# Remote.net
KiCad netlist of a schematic drawn in Altium Designer
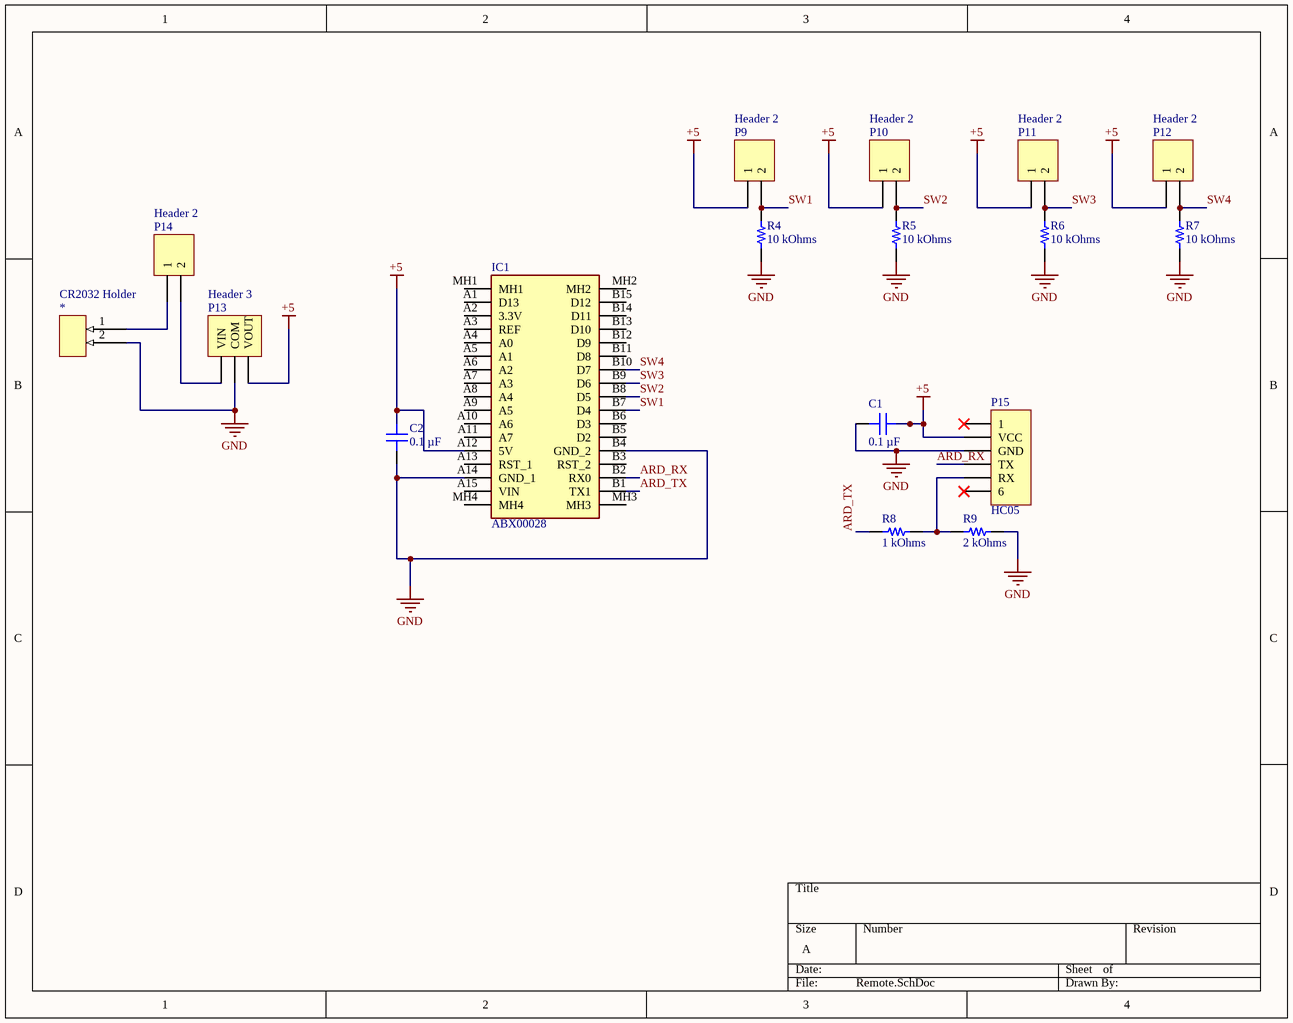
[diagram p0: Remote.SchDoc]

(export (version "E")
  (design (tool "Eeschema 10.0.6"))
  (components
    (comp (ref "*")
      (value "CR2032 Holder")
      (footprint "CR2032 Holder-Footprint-1")
      (description "Coin cell battery holder")
      (libsource (lib "Donados") (part "CR2032 Holder-Symbol-1"))
    )
    (comp (ref "C1")
      (value "0.1 µF")
      (footprint "CAP 1206_3216 - 0.8MM")
      (description "CAP CER 0.1UF 50V Y5V 1206")
      (fields (field (name "PART NUMBER") "CC1206MRY5V9BB104") (field (name "MANUFACTURER") "Yageo"))
      (libsource (lib "Celestial Altium Library - altium_library") (part "Capacitor"))
    )
    (comp (ref "C2")
      (value "0.1 µF")
      (footprint "CAP 1206_3216 - 0.8MM")
      (description "CAP CER 0.1UF 50V Y5V 1206")
      (fields (field (name "PART NUMBER") "CC1206MRY5V9BB104") (field (name "MANUFACTURER") "Yageo"))
      (libsource (lib "Celestial Altium Library - altium_library") (part "Capacitor"))
    )
    (comp (ref "IC1")
      (value "ABX00028")
      (footprint "SamacSys:ABX00028")
      (description "Integrated Circuit")
      (fields (field (name "MOUSER PART NUMBER") "782-ABX00028"))
      (libsource (lib "*") (part "ABX00028"))
    )
    (comp (ref "P9")
      (value "Header 2")
      (footprint "HDR1X2")
      (description "Header, 2-Pin")
      (fields (field (name "PUBLISHER") "Altium Limited"))
      (libsource (lib "Miscellaneous Connectors") (part "Header 2"))
    )
    (comp (ref "P10")
      (value "Header 2")
      (footprint "HDR1X2")
      (description "Header, 2-Pin")
      (fields (field (name "PUBLISHER") "Altium Limited"))
      (libsource (lib "Miscellaneous Connectors") (part "Header 2"))
    )
    (comp (ref "P11")
      (value "Header 2")
      (footprint "HDR1X2")
      (description "Header, 2-Pin")
      (fields (field (name "PUBLISHER") "Altium Limited"))
      (libsource (lib "Miscellaneous Connectors") (part "Header 2"))
    )
    (comp (ref "P12")
      (value "Header 2")
      (footprint "HDR1X2")
      (description "Header, 2-Pin")
      (fields (field (name "PUBLISHER") "Altium Limited"))
      (libsource (lib "Miscellaneous Connectors") (part "Header 2"))
    )
    (comp (ref "P13")
      (value "Header 3")
      (footprint "HDR1X3")
      (description "Header, 3-Pin")
      (fields (field (name "PUBLISHER") "Altium Limited"))
      (libsource (lib "Miscellaneous Connectors") (part "Header 3"))
    )
    (comp (ref "P14")
      (value "Header 2")
      (footprint "HDR1X2")
      (description "Header, 2-Pin")
      (fields (field (name "PUBLISHER") "Altium Limited"))
      (libsource (lib "Miscellaneous Connectors") (part "Header 2"))
    )
    (comp (ref "P15")
      (value "HC05")
      (footprint "HDR1X6")
      (description "Header, 6-Pin")
      (fields (field (name "PUBLISHER") "Altium Limited"))
      (libsource (lib "Miscellaneous Connectors") (part "Header 6"))
    )
    (comp (ref "R4")
      (value "10 kOhms")
      (footprint "RES 1206_3216")
      (description "RES SMD 10K OHM 1% 1/4W 1206")
      (fields
        (field (name "PART NUMBER") "CRG1206F10K")
        (field (name "MANUFACTURER") "TE Connectivity Passive Product")
      )
      (libsource (lib "Celestial Altium Library - altium_library") (part "Resistor"))
    )
    (comp (ref "R5")
      (value "10 kOhms")
      (footprint "RES 1206_3216")
      (description "RES SMD 10K OHM 1% 1/4W 1206")
      (fields
        (field (name "PART NUMBER") "CRG1206F10K")
        (field (name "MANUFACTURER") "TE Connectivity Passive Product")
      )
      (libsource (lib "Celestial Altium Library - altium_library") (part "Resistor"))
    )
    (comp (ref "R6")
      (value "10 kOhms")
      (footprint "RES 1206_3216")
      (description "RES SMD 10K OHM 1% 1/4W 1206")
      (fields
        (field (name "PART NUMBER") "CRG1206F10K")
        (field (name "MANUFACTURER") "TE Connectivity Passive Product")
      )
      (libsource (lib "Celestial Altium Library - altium_library") (part "Resistor"))
    )
    (comp (ref "R7")
      (value "10 kOhms")
      (footprint "RES 1206_3216")
      (description "RES SMD 10K OHM 1% 1/4W 1206")
      (fields
        (field (name "PART NUMBER") "CRG1206F10K")
        (field (name "MANUFACTURER") "TE Connectivity Passive Product")
      )
      (libsource (lib "Celestial Altium Library - altium_library") (part "Resistor"))
    )
    (comp (ref "R8")
      (value "1 kOhms")
      (footprint "RES 1206_3216")
      (description "RES 1K OHM 0.1% 1/8W 1206")
      (fields
        (field (name "PART NUMBER") "RNCS1206BKE1K00")
        (field (name "MANUFACTURER") "Stackpole Electronics Inc")
      )
      (libsource (lib "Celestial Altium Library - altium_library") (part "Resistor"))
    )
    (comp (ref "R9")
      (value "2 kOhms")
      (footprint "RES 1206_3216")
      (description "RES SMD 2K OHM 5% 1/4W 1206")
      (fields (field (name "PART NUMBER") "AC1206JR-072KL") (field (name "MANUFACTURER") "Yageo"))
      (libsource (lib "Celestial Altium Library - altium_library") (part "Resistor"))
    )
  )
  (nets
    (net (code "1") (name "+5") (class "Default")
      (node (ref "C1") (pin "2") (pinfunction "2_2") (pintype "passive"))
      (node (ref "C2") (pin "2") (pinfunction "2_2") (pintype "passive"))
      (node (ref "IC1") (pin "A12") (pinfunction "5V_A12") (pintype "passive"))
      (node (ref "P10") (pin "1") (pinfunction "1_1") (pintype "passive"))
      (node (ref "P11") (pin "1") (pinfunction "1_1") (pintype "passive"))
      (node (ref "P12") (pin "1") (pinfunction "1_1") (pintype "passive"))
      (node (ref "P13") (pin "3") (pinfunction "VOUT_3") (pintype "passive"))
      (node (ref "P15") (pin "2") (pinfunction "VCC_2") (pintype "passive"))
      (node (ref "P9") (pin "1") (pinfunction "1_1") (pintype "passive"))
    )
    (net (code "2") (name "/ARD_RX") (class "Default")
      (node (ref "IC1") (pin "B2") (pinfunction "RX0_B2") (pintype "passive"))
      (node (ref "P15") (pin "4") (pinfunction "TX_4") (pintype "passive"))
    )
    (net (code "3") (name "/ARD_TX") (class "Default")
      (node (ref "IC1") (pin "B1") (pinfunction "TX1_B1") (pintype "passive"))
      (node (ref "R8") (pin "1") (pinfunction "1_1") (pintype "passive"))
    )
    (net (code "4") (name "/SW1") (class "Default")
      (node (ref "IC1") (pin "B7") (pinfunction "D4_B7") (pintype "passive"))
      (node (ref "P9") (pin "2") (pinfunction "2_2") (pintype "passive"))
      (node (ref "R4") (pin "2") (pinfunction "2_2") (pintype "passive"))
    )
    (net (code "5") (name "/SW2") (class "Default")
      (node (ref "IC1") (pin "B8") (pinfunction "D5_B8") (pintype "passive"))
      (node (ref "P10") (pin "2") (pinfunction "2_2") (pintype "passive"))
      (node (ref "R5") (pin "2") (pinfunction "2_2") (pintype "passive"))
    )
    (net (code "6") (name "/SW3") (class "Default")
      (node (ref "IC1") (pin "B9") (pinfunction "D6_B9") (pintype "passive"))
      (node (ref "P11") (pin "2") (pinfunction "2_2") (pintype "passive"))
      (node (ref "R6") (pin "2") (pinfunction "2_2") (pintype "passive"))
    )
    (net (code "7") (name "/SW4") (class "Default")
      (node (ref "IC1") (pin "B10") (pinfunction "D7_B10") (pintype "passive"))
      (node (ref "P12") (pin "2") (pinfunction "2_2") (pintype "passive"))
      (node (ref "R7") (pin "2") (pinfunction "2_2") (pintype "passive"))
    )
    (net (code "8") (name "GND") (class "Default")
      (node (ref "*") (pin "2") (pintype "input"))
      (node (ref "C1") (pin "1") (pinfunction "1_1") (pintype "passive"))
      (node (ref "C2") (pin "1") (pinfunction "1_1") (pintype "passive"))
      (node (ref "IC1") (pin "A14") (pinfunction "GND_1_A14") (pintype "passive"))
      (node (ref "IC1") (pin "B4") (pinfunction "GND_2_B4") (pintype "passive"))
      (node (ref "P13") (pin "2") (pinfunction "COM_2") (pintype "passive"))
      (node (ref "P15") (pin "3") (pinfunction "GND_3") (pintype "passive"))
      (node (ref "R4") (pin "1") (pinfunction "1_1") (pintype "passive"))
      (node (ref "R5") (pin "1") (pinfunction "1_1") (pintype "passive"))
      (node (ref "R6") (pin "1") (pinfunction "1_1") (pintype "passive"))
      (node (ref "R7") (pin "1") (pinfunction "1_1") (pintype "passive"))
      (node (ref "R9") (pin "2") (pinfunction "2_2") (pintype "passive"))
    )
    (net (code "9") (name "Net-(*-Pad1)") (class "Default")
      (node (ref "*") (pin "1") (pintype "input"))
      (node (ref "P14") (pin "1") (pinfunction "1_1") (pintype "passive"))
    )
    (net (code "10") (name "Net-(P13-VIN)") (class "Default")
      (node (ref "P13") (pin "1") (pinfunction "VIN_1") (pintype "passive"))
      (node (ref "P14") (pin "2") (pinfunction "2_2") (pintype "passive"))
    )
    (net (code "11") (name "Net-(P15-RX)") (class "Default")
      (node (ref "P15") (pin "5") (pinfunction "RX_5") (pintype "passive"))
      (node (ref "R8") (pin "2") (pinfunction "2_2") (pintype "passive"))
      (node (ref "R9") (pin "1") (pinfunction "1_1") (pintype "passive"))
    )
    (net (code "12") (name "unconnected-(IC1-3.3V-PadA2)") (class "Default")
      (node (ref "IC1") (pin "A2") (pinfunction "3.3V_A2") (pintype "passive"))
    )
    (net (code "13") (name "unconnected-(IC1-A0-PadA4)") (class "Default")
      (node (ref "IC1") (pin "A4") (pinfunction "A0_A4") (pintype "passive"))
    )
    (net (code "14") (name "unconnected-(IC1-A1-PadA5)") (class "Default")
      (node (ref "IC1") (pin "A5") (pinfunction "A1_A5") (pintype "passive"))
    )
    (net (code "15") (name "unconnected-(IC1-A2-PadA6)") (class "Default")
      (node (ref "IC1") (pin "A6") (pinfunction "A2_A6") (pintype "passive"))
    )
    (net (code "16") (name "unconnected-(IC1-A3-PadA7)") (class "Default")
      (node (ref "IC1") (pin "A7") (pinfunction "A3_A7") (pintype "passive"))
    )
    (net (code "17") (name "unconnected-(IC1-A4-PadA8)") (class "Default")
      (node (ref "IC1") (pin "A8") (pinfunction "A4_A8") (pintype "passive"))
    )
    (net (code "18") (name "unconnected-(IC1-A5-PadA9)") (class "Default")
      (node (ref "IC1") (pin "A9") (pinfunction "A5_A9") (pintype "passive"))
    )
    (net (code "19") (name "unconnected-(IC1-A6-PadA10)") (class "Default")
      (node (ref "IC1") (pin "A10") (pinfunction "A6_A10") (pintype "passive"))
    )
    (net (code "20") (name "unconnected-(IC1-A7-PadA11)") (class "Default")
      (node (ref "IC1") (pin "A11") (pinfunction "A7_A11") (pintype "passive"))
    )
    (net (code "21") (name "unconnected-(IC1-D2-PadB5)") (class "Default")
      (node (ref "IC1") (pin "B5") (pinfunction "D2_B5") (pintype "passive"))
    )
    (net (code "22") (name "unconnected-(IC1-D3-PadB6)") (class "Default")
      (node (ref "IC1") (pin "B6") (pinfunction "D3_B6") (pintype "passive"))
    )
    (net (code "23") (name "unconnected-(IC1-D8-PadB11)") (class "Default")
      (node (ref "IC1") (pin "B11") (pinfunction "D8_B11") (pintype "passive"))
    )
    (net (code "24") (name "unconnected-(IC1-D9-PadB12)") (class "Default")
      (node (ref "IC1") (pin "B12") (pinfunction "D9_B12") (pintype "passive"))
    )
    (net (code "25") (name "unconnected-(IC1-D10-PadB13)") (class "Default")
      (node (ref "IC1") (pin "B13") (pinfunction "D10_B13") (pintype "passive"))
    )
    (net (code "26") (name "unconnected-(IC1-D11-PadB14)") (class "Default")
      (node (ref "IC1") (pin "B14") (pinfunction "D11_B14") (pintype "passive"))
    )
    (net (code "27") (name "unconnected-(IC1-D12-PadB15)") (class "Default")
      (node (ref "IC1") (pin "B15") (pinfunction "D12_B15") (pintype "passive"))
    )
    (net (code "28") (name "unconnected-(IC1-D13-PadA1)") (class "Default")
      (node (ref "IC1") (pin "A1") (pinfunction "D13_A1") (pintype "passive"))
    )
    (net (code "29") (name "unconnected-(IC1-PadMH1)") (class "Default")
      (node (ref "IC1") (pin "MH1") (pinfunction "MH1_MH1") (pintype "passive"))
    )
    (net (code "30") (name "unconnected-(IC1-PadMH2)") (class "Default")
      (node (ref "IC1") (pin "MH2") (pinfunction "MH2_MH2") (pintype "passive"))
    )
    (net (code "31") (name "unconnected-(IC1-PadMH3)") (class "Default")
      (node (ref "IC1") (pin "MH3") (pinfunction "MH3_MH3") (pintype "passive"))
    )
    (net (code "32") (name "unconnected-(IC1-PadMH4)") (class "Default")
      (node (ref "IC1") (pin "MH4") (pinfunction "MH4_MH4") (pintype "passive"))
    )
    (net (code "33") (name "unconnected-(IC1-REF-PadA3)") (class "Default")
      (node (ref "IC1") (pin "A3") (pinfunction "REF_A3") (pintype "passive"))
    )
    (net (code "34") (name "unconnected-(IC1-RST_1-PadA13)") (class "Default")
      (node (ref "IC1") (pin "A13") (pinfunction "RST_1_A13") (pintype "passive"))
    )
    (net (code "35") (name "unconnected-(IC1-RST_2-PadB3)") (class "Default")
      (node (ref "IC1") (pin "B3") (pinfunction "RST_2_B3") (pintype "passive"))
    )
    (net (code "36") (name "unconnected-(IC1-VIN-PadA15)") (class "Default")
      (node (ref "IC1") (pin "A15") (pinfunction "VIN_A15") (pintype "passive"))
    )
    (net (code "37") (name "unconnected-(P15-Pad1)") (class "Default")
      (node (ref "P15") (pin "1") (pinfunction "1_1") (pintype "passive+no_connect"))
    )
    (net (code "38") (name "unconnected-(P15-Pad6)") (class "Default")
      (node (ref "P15") (pin "6") (pinfunction "6_6") (pintype "passive+no_connect"))
    )
  )
)
